# design.net
KiCad netlist of a schematic drawn in Altium Designer
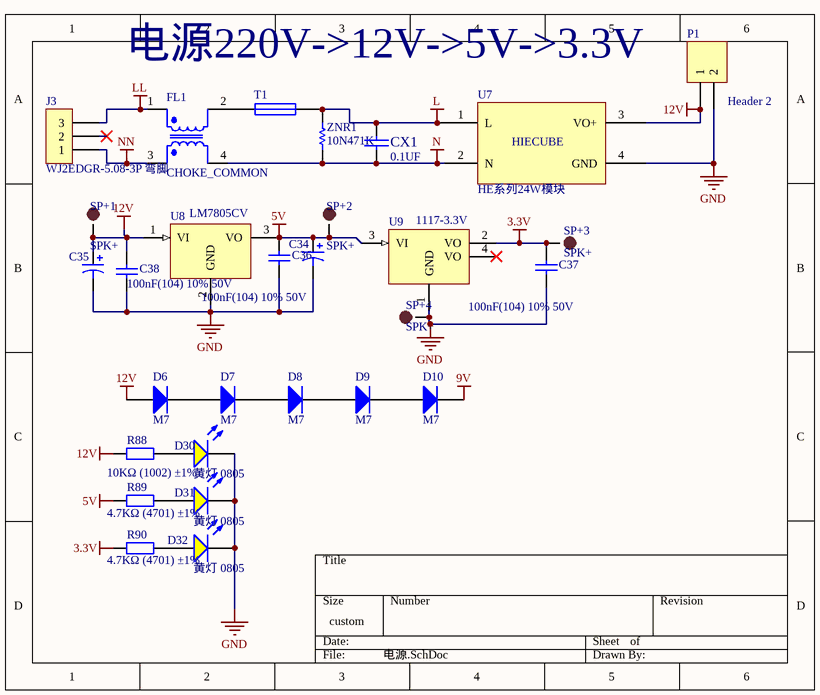
[diagram p0: 电源.SchDoc]

(export (version "E")
  (design (tool "Eeschema 10.0.6"))
  (components
    (comp (ref "C34")
      (value "Cap Pol1")
      (footprint "CAP1000UF")
      (description "Polarized Capacitor (Radial)")
      (fields (field (name "PUBLISHER") "Altium Limited"))
      (libsource (lib "Miscellaneous Devices") (part "Cap Pol1"))
    )
    (comp (ref "C35")
      (value "Cap Pol1")
      (footprint "CAP1000UF")
      (description "Polarized Capacitor (Radial)")
      (fields (field (name "PUBLISHER") "Altium Limited"))
      (libsource (lib "Miscellaneous Devices") (part "Cap Pol1"))
    )
    (comp (ref "C36")
      (value "100nF(104) 10% 50V")
      (footprint "0805_C")
      (description "贴片电容")
      (libsource (lib "Cap") (part "0805 100nF(104) 10% 50V"))
    )
    (comp (ref "C37")
      (value "100nF(104) 10% 50V")
      (footprint "0805_C")
      (description "贴片电容")
      (libsource (lib "Cap") (part "0805 100nF(104) 10% 50V"))
    )
    (comp (ref "C38")
      (value "100nF(104) 10% 50V")
      (footprint "0805_C")
      (description "贴片电容")
      (libsource (lib "Cap") (part "0805 100nF(104) 10% 50V"))
    )
    (comp (ref "CX1")
      (value "0.1UF")
      (footprint "0.1uf 安规")
      (description "Capacitor")
      (libsource (lib "*") (part "CAP"))
    )
    (comp (ref "D6")
      (value "M7")
      (footprint "SMA(DO-214AC)_S1")
      (description "二极管")
      (libsource (lib "Diode") (part "SMA(DO-214AC) M7"))
    )
    (comp (ref "D7")
      (value "M7")
      (footprint "SMA(DO-214AC)_S1")
      (description "二极管")
      (libsource (lib "Diode") (part "SMA(DO-214AC) M7"))
    )
    (comp (ref "D8")
      (value "M7")
      (footprint "SMA(DO-214AC)_S1")
      (description "二极管")
      (libsource (lib "Diode") (part "SMA(DO-214AC) M7"))
    )
    (comp (ref "D9")
      (value "M7")
      (footprint "SMA(DO-214AC)_S1")
      (description "二极管")
      (libsource (lib "Diode") (part "SMA(DO-214AC) M7"))
    )
    (comp (ref "D10")
      (value "M7")
      (footprint "SMA(DO-214AC)_S1")
      (description "二极管")
      (libsource (lib "Diode") (part "SMA(DO-214AC) M7"))
    )
    (comp (ref "D30")
      (value "黄灯 0805")
      (footprint "0805_LED_S1")
      (description "发光二极管")
      (libsource (lib "LED") (part "0805 黄灯"))
    )
    (comp (ref "D31")
      (value "黄灯 0805")
      (footprint "0805_LED_S1")
      (description "发光二极管")
      (libsource (lib "LED") (part "0805 黄灯"))
    )
    (comp (ref "D32")
      (value "黄灯 0805")
      (footprint "0805_LED_S1")
      (description "发光二极管")
      (libsource (lib "LED") (part "0805 黄灯"))
    )
    (comp (ref "FL1")
      (value "CHOKE_COMMON")
      (footprint "CHOKE-13x10")
      (description "Choke")
      (libsource (lib "淘宝封装") (part "CHOKE_COMMON"))
    )
    (comp (ref "J3")
      (value "WJ2EDGR-5.08-3P 弯脚")
      (footprint "Connector:WJ2EDGR-5.08-3")
      (description "2EDG连接器")
      (libsource (lib "Connector") (part "WJ2EDGR-5.08-3P 弯脚"))
    )
    (comp (ref "P1")
      (value "Header 2")
      (footprint "WJ2EDGR-5.08-2")
      (description "Header, 2-Pin")
      (fields (field (name "PUBLISHER") "Altium Limited"))
      (libsource (lib "Miscellaneous Connectors") (part "Header 2"))
    )
    (comp (ref "R88")
      (value "10KΩ (1002) ±1%")
      (footprint "0805_R")
      (description "贴片电阻")
      (libsource (lib "RES") (part "0805 10KΩ (1002) 1%"))
    )
    (comp (ref "R89")
      (value "4.7KΩ (4701) ±1%")
      (footprint "0805_R")
      (description "贴片电阻")
      (libsource (lib "RES") (part "0805 4.7KΩ (4701) 1%"))
    )
    (comp (ref "R90")
      (value "4.7KΩ (4701) ±1%")
      (footprint "0805_R")
      (description "贴片电阻")
      (libsource (lib "RES") (part "0805 4.7KΩ (4701) 1%"))
    )
    (comp (ref "SP+1")
      (value "SPK+")
      (footprint "TP-1.5")
      (description "测试点")
      (libsource (lib "EXPLORER") (part "TEST-POINT"))
    )
    (comp (ref "SP+2")
      (value "SPK+")
      (footprint "TP-1.5")
      (description "测试点")
      (libsource (lib "EXPLORER") (part "TEST-POINT"))
    )
    (comp (ref "SP+3")
      (value "SPK+")
      (footprint "TP-1.5")
      (description "测试点")
      (libsource (lib "EXPLORER") (part "TEST-POINT"))
    )
    (comp (ref "SP+4")
      (value "SPK+")
      (footprint "TP-1.5")
      (description "测试点")
      (libsource (lib "EXPLORER") (part "TEST-POINT"))
    )
    (comp (ref "T1")
      (value "Fuse 1")
      (footprint "392保险丝")
      (description "Fuse")
      (fields (field (name "PUBLISHER") "Altium Limited"))
      (libsource (lib "Miscellaneous Devices") (part "Fuse 1"))
    )
    (comp (ref "U7")
      (value "HE系列24W模块")
      (footprint "ac转dc")
      (libsource (lib "DEMO板原理图封装") (part "HE系列24W模块"))
    )
    (comp (ref "U8")
      (value "LM7805CV")
      (footprint "TO-220散热片")
      (description "Linear Regulator")
      (libsource (lib "淘宝封装") (part "78xx"))
    )
    (comp (ref "U9")
      (value "1117-3.3V")
      (footprint "SOT-223")
      (description "Linear Regulator")
      (libsource (lib "集成库") (part "1117"))
    )
    (comp (ref "ZNR1")
      (value "10N471K")
      (footprint "10N471K")
      (description "Resistor")
      (fields (field (name "PUBLISHER") "Altium Limited"))
      (libsource (lib "Miscellaneous Devices") (part "Res1"))
    )
  )
  (nets
    (net (code "1") (name "3.3V") (class "Default")
      (node (ref "C37") (pin "2") (pinfunction "2_2") (pintype "passive"))
      (node (ref "R90") (pin "1") (pinfunction "1_1") (pintype "passive"))
      (node (ref "SP+3") (pin "1") (pinfunction "1_1") (pintype "passive"))
      (node (ref "U9") (pin "2") (pinfunction "VO_2") (pintype "power_in"))
    )
    (net (code "2") (name "5V") (class "Default")
      (node (ref "C34") (pin "1") (pinfunction "1_1") (pintype "passive"))
      (node (ref "C36") (pin "2") (pinfunction "2_2") (pintype "passive"))
      (node (ref "R89") (pin "1") (pinfunction "1_1") (pintype "passive"))
      (node (ref "SP+2") (pin "1") (pinfunction "1_1") (pintype "passive"))
      (node (ref "U8") (pin "3") (pinfunction "VO_3") (pintype "power_in"))
      (node (ref "U9") (pin "3") (pinfunction "VI_3") (pintype "input"))
    )
    (net (code "3") (name "9V") (class "Default")
      (node (ref "D10") (pin "2") (pinfunction "K_2") (pintype "passive"))
    )
    (net (code "4") (name "12V") (class "Default")
      (node (ref "C35") (pin "1") (pinfunction "1_1") (pintype "passive"))
      (node (ref "C38") (pin "2") (pinfunction "2_2") (pintype "passive"))
      (node (ref "D6") (pin "1") (pinfunction "A_1") (pintype "passive"))
      (node (ref "P1") (pin "1") (pinfunction "1_1") (pintype "passive"))
      (node (ref "R88") (pin "1") (pinfunction "1_1") (pintype "passive"))
      (node (ref "SP+1") (pin "1") (pinfunction "1_1") (pintype "passive"))
      (node (ref "U7") (pin "3") (pinfunction "VO+_3") (pintype "passive"))
      (node (ref "U8") (pin "1") (pinfunction "VI_1") (pintype "input"))
    )
    (net (code "5") (name "GND") (class "Default")
      (node (ref "C34") (pin "2") (pinfunction "2_2") (pintype "passive"))
      (node (ref "C35") (pin "2") (pinfunction "2_2") (pintype "passive"))
      (node (ref "C36") (pin "1") (pinfunction "1_1") (pintype "passive"))
      (node (ref "C37") (pin "1") (pinfunction "1_1") (pintype "passive"))
      (node (ref "C38") (pin "1") (pinfunction "1_1") (pintype "passive"))
      (node (ref "D30") (pin "K") (pinfunction "K_K") (pintype "passive"))
      (node (ref "D31") (pin "K") (pinfunction "K_K") (pintype "passive"))
      (node (ref "D32") (pin "K") (pinfunction "K_K") (pintype "passive"))
      (node (ref "P1") (pin "2") (pinfunction "2_2") (pintype "passive"))
      (node (ref "SP+4") (pin "1") (pinfunction "1_1") (pintype "passive"))
      (node (ref "U7") (pin "4") (pinfunction "GND_4") (pintype "passive"))
      (node (ref "U8") (pin "2") (pinfunction "GND_2") (pintype "power_in"))
      (node (ref "U9") (pin "1") (pinfunction "GND_1") (pintype "power_in"))
    )
    (net (code "6") (name "L") (class "Default")
      (node (ref "CX1") (pin "2") (pinfunction "2_2") (pintype "passive"))
      (node (ref "T1") (pin "2") (pinfunction "2_2") (pintype "passive"))
      (node (ref "U7") (pin "1") (pinfunction "L_1") (pintype "passive"))
      (node (ref "ZNR1") (pin "1") (pinfunction "1_1") (pintype "passive"))
    )
    (net (code "7") (name "LL") (class "Default")
      (node (ref "FL1") (pin "1") (pinfunction "1_1") (pintype "passive"))
      (node (ref "J3") (pin "3") (pinfunction "3_3") (pintype "passive"))
    )
    (net (code "8") (name "N") (class "Default")
      (node (ref "CX1") (pin "1") (pinfunction "1_1") (pintype "passive"))
      (node (ref "FL1") (pin "4") (pinfunction "4_4") (pintype "passive"))
      (node (ref "U7") (pin "2") (pinfunction "N_2") (pintype "passive"))
      (node (ref "ZNR1") (pin "2") (pinfunction "2_2") (pintype "passive"))
    )
    (net (code "9") (name "NN") (class "Default")
      (node (ref "FL1") (pin "3") (pinfunction "3_3") (pintype "passive"))
      (node (ref "J3") (pin "1") (pinfunction "1_1") (pintype "passive"))
    )
    (net (code "10") (name "Net-(D6-K)") (class "Default")
      (node (ref "D6") (pin "2") (pinfunction "K_2") (pintype "passive"))
      (node (ref "D7") (pin "1") (pinfunction "A_1") (pintype "passive"))
    )
    (net (code "11") (name "Net-(D7-K)") (class "Default")
      (node (ref "D7") (pin "2") (pinfunction "K_2") (pintype "passive"))
      (node (ref "D8") (pin "1") (pinfunction "A_1") (pintype "passive"))
    )
    (net (code "12") (name "Net-(D8-K)") (class "Default")
      (node (ref "D8") (pin "2") (pinfunction "K_2") (pintype "passive"))
      (node (ref "D9") (pin "1") (pinfunction "A_1") (pintype "passive"))
    )
    (net (code "13") (name "Net-(D10-A)") (class "Default")
      (node (ref "D10") (pin "1") (pinfunction "A_1") (pintype "passive"))
      (node (ref "D9") (pin "2") (pinfunction "K_2") (pintype "passive"))
    )
    (net (code "14") (name "Net-(D30-PadA)") (class "Default")
      (node (ref "D30") (pin "A") (pinfunction "A_A") (pintype "passive"))
      (node (ref "R88") (pin "2") (pinfunction "2_2") (pintype "passive"))
    )
    (net (code "15") (name "Net-(D31-PadA)") (class "Default")
      (node (ref "D31") (pin "A") (pinfunction "A_A") (pintype "passive"))
      (node (ref "R89") (pin "2") (pinfunction "2_2") (pintype "passive"))
    )
    (net (code "16") (name "Net-(D32-PadA)") (class "Default")
      (node (ref "D32") (pin "A") (pinfunction "A_A") (pintype "passive"))
      (node (ref "R90") (pin "2") (pinfunction "2_2") (pintype "passive"))
    )
    (net (code "17") (name "Net-(FL1-Pad2)") (class "Default")
      (node (ref "FL1") (pin "2") (pinfunction "2_2") (pintype "passive"))
      (node (ref "T1") (pin "1") (pinfunction "1_1") (pintype "passive"))
    )
    (net (code "18") (name "unconnected-(J3-Pad2)") (class "Default")
      (node (ref "J3") (pin "2") (pinfunction "2_2") (pintype "passive+no_connect"))
    )
    (net (code "19") (name "unconnected-(U9-VO-Pad4)") (class "Default")
      (node (ref "U9") (pin "4") (pinfunction "VO_4") (pintype "power_in+no_connect"))
    )
  )
)
